# PIC.net
KiCad netlist of a schematic drawn in Altium Designer
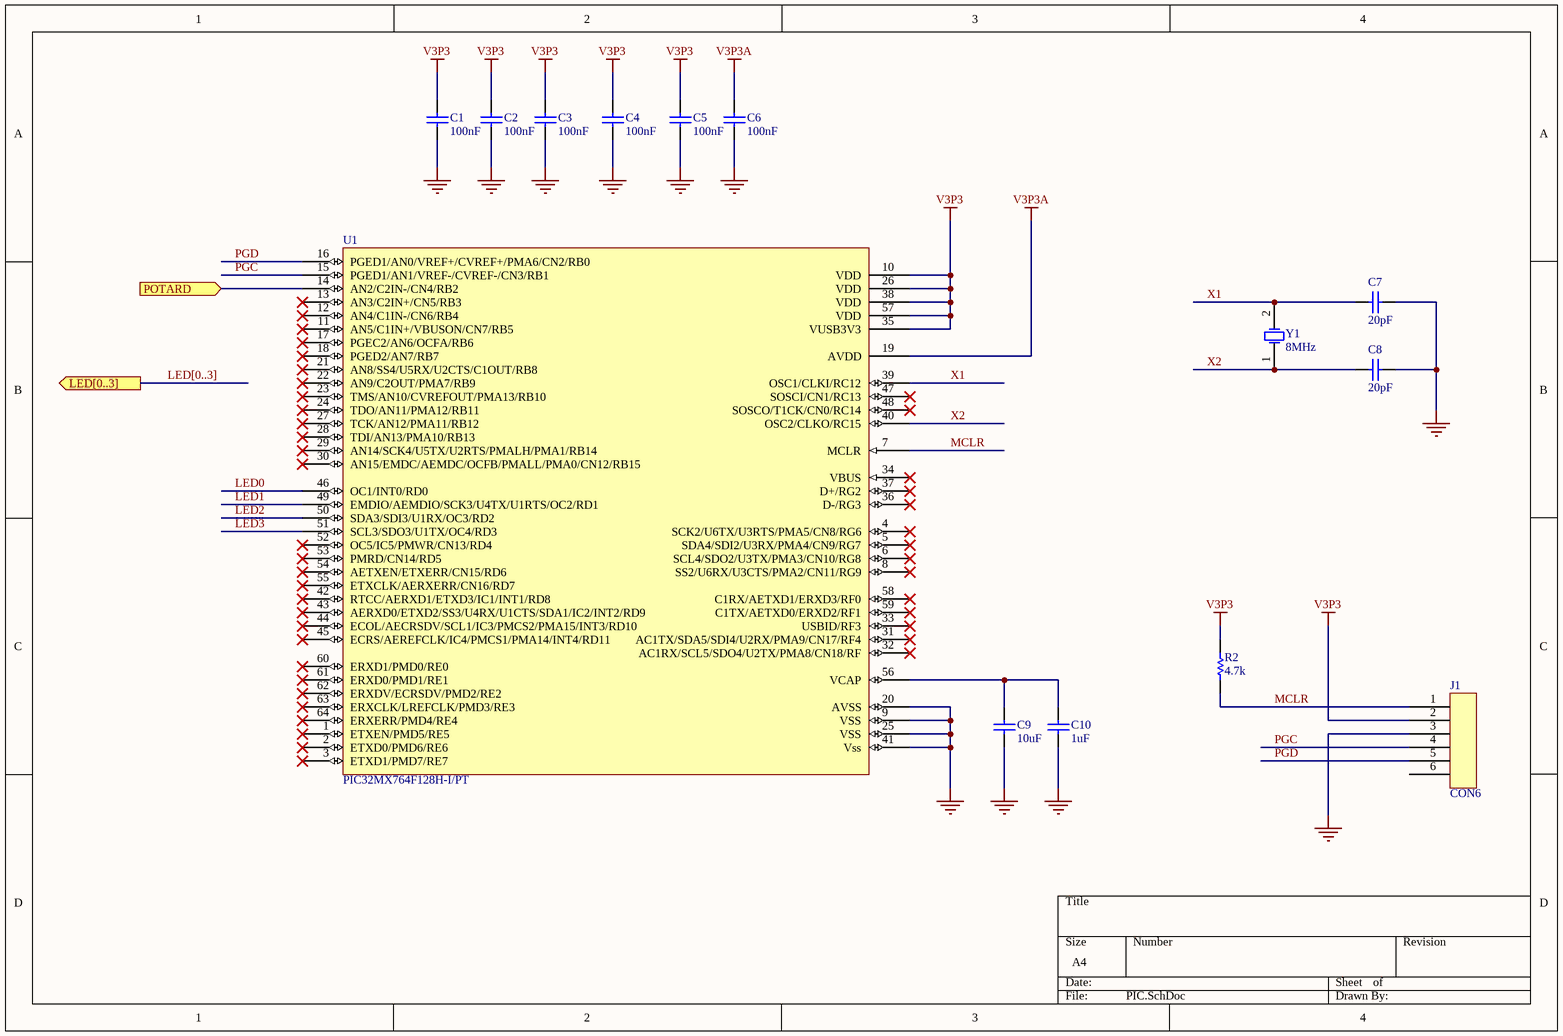
[diagram p0: PIC.SchDoc]

(export (version "E")
  (design (tool "Eeschema 10.0.6"))
  (components
    (comp (ref "C1")
      (value "100nF")
      (footprint "CAPC1608N")
      (description "Capacitor")
      (fields (field (name "PUBLISHER") "Altium Limited"))
      (libsource (lib "Miscellaneous Devices") (part "Cap"))
    )
    (comp (ref "C2")
      (value "100nF")
      (footprint "CAPC1608N")
      (description "Capacitor")
      (fields (field (name "PUBLISHER") "Altium Limited"))
      (libsource (lib "Miscellaneous Devices") (part "Cap"))
    )
    (comp (ref "C3")
      (value "100nF")
      (footprint "CAPC1608N")
      (description "Capacitor")
      (fields (field (name "PUBLISHER") "Altium Limited"))
      (libsource (lib "Miscellaneous Devices") (part "Cap"))
    )
    (comp (ref "C4")
      (value "100nF")
      (footprint "CAPC1608N")
      (description "Capacitor")
      (fields (field (name "PUBLISHER") "Altium Limited"))
      (libsource (lib "Miscellaneous Devices") (part "Cap"))
    )
    (comp (ref "C5")
      (value "100nF")
      (footprint "CAPC1608N")
      (description "Capacitor")
      (fields (field (name "PUBLISHER") "Altium Limited"))
      (libsource (lib "Miscellaneous Devices") (part "Cap"))
    )
    (comp (ref "C6")
      (value "100nF")
      (footprint "CAPC1608N")
      (description "Capacitor")
      (fields (field (name "PUBLISHER") "Altium Limited"))
      (libsource (lib "Miscellaneous Devices") (part "Cap"))
    )
    (comp (ref "C7")
      (value "20pF")
      (footprint "CAPC1608N")
      (description "Capacitor")
      (fields (field (name "PUBLISHER") "Altium Limited"))
      (libsource (lib "Miscellaneous Devices") (part "Cap"))
    )
    (comp (ref "C8")
      (value "20pF")
      (footprint "CAPC1608N")
      (description "Capacitor")
      (fields (field (name "PUBLISHER") "Altium Limited"))
      (libsource (lib "Miscellaneous Devices") (part "Cap"))
    )
    (comp (ref "C9")
      (value "10uF")
      (footprint "CAPC2012N")
      (description "Capacitor")
      (fields (field (name "PUBLISHER") "Altium Limited"))
      (libsource (lib "Miscellaneous Devices") (part "Cap"))
    )
    (comp (ref "C10")
      (value "1uF")
      (footprint "CAPC1608N")
      (description "Capacitor")
      (fields (field (name "PUBLISHER") "Altium Limited"))
      (libsource (lib "Miscellaneous Devices") (part "Cap"))
    )
    (comp (ref "J1") (value "CON6") (footprint "RJ12_90") (libsource (lib "Schlib1") (part "CON6")))
    (comp (ref "R2")
      (value "4.7k")
      (footprint "RESC1608N")
      (description "Resistor")
      (fields (field (name "PUBLISHER") "Altium Limited"))
      (libsource (lib "Miscellaneous Devices") (part "Res1"))
    )
    (comp (ref "U1")
      (value "PIC32MX764F128H-I/PT")
      (footprint "QFP50P1200X1200X120-64")
      (description "PIC32MX764F128H")
      (libsource (lib "Schlib1") (part "PIC32MX764F128H"))
    )
    (comp (ref "Y1")
      (value "8MHz")
      (footprint "XTAL139X50X45")
      (description "Crystal Oscillator")
      (fields (field (name "PUBLISHER") "Altium Limited"))
      (libsource (lib "Miscellaneous Devices") (part "XTAL"))
    )
  )
  (nets
    (net (code "1") (name "/LED0") (class "Default")
      (node (ref "U1") (pin "46") (pinfunction "OC1/INT0/RD0_46") (pintype "bidirectional"))
    )
    (net (code "2") (name "/LED1") (class "Default")
      (node (ref "U1") (pin "49") (pinfunction "EMDIO/AEMDIO/SCK3/U4TX/U1RTS/OC2/RD1_49") (pintype "bidirectional"))
    )
    (net (code "3") (name "/LED2") (class "Default")
      (node (ref "U1") (pin "50") (pinfunction "SDA3/SDI3/U1RX/OC3/RD2_50") (pintype "bidirectional"))
    )
    (net (code "4") (name "/LED3") (class "Default")
      (node (ref "U1") (pin "51") (pinfunction "SCL3/SDO3/U1TX/OC4/RD3_51") (pintype "bidirectional"))
    )
    (net (code "6") (name "/MCLR") (class "Default")
      (node (ref "J1") (pin "1") (pintype "power_in"))
      (node (ref "R2") (pin "1") (pinfunction "1_1") (pintype "passive"))
      (node (ref "U1") (pin "7") (pinfunction "MCLR_7") (pintype "input"))
    )
    (net (code "7") (name "/PGC") (class "Default")
      (node (ref "J1") (pin "4") (pintype "power_in"))
      (node (ref "U1") (pin "15") (pinfunction "PGED1/AN1/VREF-/CVREF-/CN3/RB1_15") (pintype "bidirectional"))
    )
    (net (code "8") (name "/PGD") (class "Default")
      (node (ref "J1") (pin "5") (pintype "power_in"))
      (node (ref "U1") (pin "16") (pinfunction "PGED1/AN0/VREF+/CVREF+/PMA6/CN2/RB0_16") (pintype "bidirectional"))
    )
    (net (code "9") (name "/POTARD") (class "Default")
      (node (ref "U1") (pin "14") (pinfunction "AN2/C2IN-/CN4/RB2_14") (pintype "bidirectional"))
    )
    (net (code "10") (name "/X1") (class "Default")
      (node (ref "C7") (pin "1") (pinfunction "1_1") (pintype "passive"))
      (node (ref "U1") (pin "39") (pinfunction "OSC1/CLKI/RC12_39") (pintype "bidirectional"))
      (node (ref "Y1") (pin "2") (pinfunction "OSC2_2") (pintype "passive"))
    )
    (net (code "11") (name "/X2") (class "Default")
      (node (ref "C8") (pin "1") (pinfunction "1_1") (pintype "passive"))
      (node (ref "U1") (pin "40") (pinfunction "OSC2/CLKO/RC15_40") (pintype "bidirectional"))
      (node (ref "Y1") (pin "1") (pinfunction "OSC1_1") (pintype "passive"))
    )
    (net (code "12") (name "GND") (class "Default")
      (node (ref "C1") (pin "1") (pinfunction "1_1") (pintype "passive"))
      (node (ref "C10") (pin "1") (pinfunction "1_1") (pintype "passive"))
      (node (ref "C2") (pin "1") (pinfunction "1_1") (pintype "passive"))
      (node (ref "C3") (pin "1") (pinfunction "1_1") (pintype "passive"))
      (node (ref "C4") (pin "1") (pinfunction "1_1") (pintype "passive"))
      (node (ref "C5") (pin "1") (pinfunction "1_1") (pintype "passive"))
      (node (ref "C6") (pin "1") (pinfunction "1_1") (pintype "passive"))
      (node (ref "C7") (pin "2") (pinfunction "2_2") (pintype "passive"))
      (node (ref "C8") (pin "2") (pinfunction "2_2") (pintype "passive"))
      (node (ref "C9") (pin "1") (pinfunction "1_1") (pintype "passive"))
      (node (ref "J1") (pin "3") (pintype "power_in"))
      (node (ref "U1") (pin "20") (pinfunction "AVSS_20") (pintype "bidirectional"))
      (node (ref "U1") (pin "25") (pinfunction "VSS_25") (pintype "bidirectional"))
      (node (ref "U1") (pin "41") (pinfunction "Vss_41") (pintype "bidirectional"))
      (node (ref "U1") (pin "9") (pinfunction "VSS_9") (pintype "bidirectional"))
    )
    (net (code "13") (name "Net-(U1-VCAP)") (class "Default")
      (node (ref "C10") (pin "2") (pinfunction "2_2") (pintype "passive"))
      (node (ref "C9") (pin "2") (pinfunction "2_2") (pintype "passive"))
      (node (ref "U1") (pin "56") (pinfunction "VCAP_56") (pintype "bidirectional"))
    )
    (net (code "14") (name "V3P3") (class "Default")
      (node (ref "C1") (pin "2") (pinfunction "2_2") (pintype "passive"))
      (node (ref "C2") (pin "2") (pinfunction "2_2") (pintype "passive"))
      (node (ref "C3") (pin "2") (pinfunction "2_2") (pintype "passive"))
      (node (ref "C4") (pin "2") (pinfunction "2_2") (pintype "passive"))
      (node (ref "C5") (pin "2") (pinfunction "2_2") (pintype "passive"))
      (node (ref "J1") (pin "2") (pintype "power_in"))
      (node (ref "R2") (pin "2") (pinfunction "2_2") (pintype "passive"))
      (node (ref "U1") (pin "10") (pinfunction "VDD_10") (pintype "power_in"))
      (node (ref "U1") (pin "26") (pinfunction "VDD_26") (pintype "power_in"))
      (node (ref "U1") (pin "35") (pinfunction "VUSB3V3_35") (pintype "power_in"))
      (node (ref "U1") (pin "38") (pinfunction "VDD_38") (pintype "power_in"))
      (node (ref "U1") (pin "57") (pinfunction "VDD_57") (pintype "power_in"))
    )
    (net (code "15") (name "V3P3A") (class "Default")
      (node (ref "C6") (pin "2") (pinfunction "2_2") (pintype "passive"))
      (node (ref "U1") (pin "19") (pinfunction "AVDD_19") (pintype "power_in"))
    )
    (net (code "16") (name "unconnected-(J1-Pad6)") (class "Default")
      (node (ref "J1") (pin "6") (pintype "power_in"))
    )
    (net (code "17") (name "unconnected-(U1-AC1RX{slash}SCL5{slash}SDO4{slash}U2TX{slash}PMA8{slash}CN18{slash}RF-Pad32)") (class "Default")
      (node (ref "U1") (pin "32") (pinfunction "AC1RX/SCL5/SDO4/U2TX/PMA8/CN18/RF_32") (pintype "bidirectional+no_connect"))
    )
    (net (code "18") (name "unconnected-(U1-AC1TX{slash}SDA5{slash}SDI4{slash}U2RX{slash}PMA9{slash}CN17{slash}RF4-Pad31)") (class "Default")
      (node (ref "U1") (pin "31") (pinfunction "AC1TX/SDA5/SDI4/U2RX/PMA9/CN17/RF4_31") (pintype "bidirectional+no_connect"))
    )
    (net (code "19") (name "unconnected-(U1-AERXD0{slash}ETXD2{slash}SS3{slash}U4RX{slash}U1CTS{slash}SDA1{slash}IC2{slash}INT2{slash}RD9-Pad43)") (class "Default")
      (node (ref "U1") (pin "43") (pinfunction "AERXD0/ETXD2/SS3/U4RX/U1CTS/SDA1/IC2/INT2/RD9_43") (pintype "bidirectional+no_connect"))
    )
    (net (code "20") (name "unconnected-(U1-AETXEN{slash}ETXERR{slash}CN15{slash}RD6-Pad54)") (class "Default")
      (node (ref "U1") (pin "54") (pinfunction "AETXEN/ETXERR/CN15/RD6_54") (pintype "bidirectional+no_connect"))
    )
    (net (code "21") (name "unconnected-(U1-AN3{slash}C2IN+{slash}CN5{slash}RB3-Pad13)") (class "Default")
      (node (ref "U1") (pin "13") (pinfunction "AN3/C2IN+/CN5/RB3_13") (pintype "bidirectional+no_connect"))
    )
    (net (code "22") (name "unconnected-(U1-AN4{slash}C1IN-{slash}CN6{slash}RB4-Pad12)") (class "Default")
      (node (ref "U1") (pin "12") (pinfunction "AN4/C1IN-/CN6/RB4_12") (pintype "bidirectional+no_connect"))
    )
    (net (code "23") (name "unconnected-(U1-AN5{slash}C1IN+{slash}VBUSON{slash}CN7{slash}RB5-Pad11)") (class "Default")
      (node (ref "U1") (pin "11") (pinfunction "AN5/C1IN+/VBUSON/CN7/RB5_11") (pintype "bidirectional+no_connect"))
    )
    (net (code "24") (name "unconnected-(U1-AN8{slash}SS4{slash}U5RX{slash}U2CTS{slash}C1OUT{slash}RB8-Pad21)") (class "Default")
      (node (ref "U1") (pin "21") (pinfunction "AN8/SS4/U5RX/U2CTS/C1OUT/RB8_21") (pintype "bidirectional+no_connect"))
    )
    (net (code "25") (name "unconnected-(U1-AN9{slash}C2OUT{slash}PMA7{slash}RB9-Pad22)") (class "Default")
      (node (ref "U1") (pin "22") (pinfunction "AN9/C2OUT/PMA7/RB9_22") (pintype "bidirectional+no_connect"))
    )
    (net (code "26") (name "unconnected-(U1-AN14{slash}SCK4{slash}U5TX{slash}U2RTS{slash}PMALH{slash}PMA1{slash}RB14-Pad29)") (class "Default")
      (node (ref "U1") (pin "29") (pinfunction "AN14/SCK4/U5TX/U2RTS/PMALH/PMA1/RB14_29") (pintype "bidirectional+no_connect"))
    )
    (net (code "27") (name "unconnected-(U1-AN15{slash}EMDC{slash}AEMDC{slash}OCFB{slash}PMALL{slash}PMA0{slash}CN12{slash}RB15-Pad30)") (class "Default")
      (node (ref "U1") (pin "30") (pinfunction "AN15/EMDC/AEMDC/OCFB/PMALL/PMA0/CN12/RB15_30") (pintype "bidirectional+no_connect"))
    )
    (net (code "28") (name "unconnected-(U1-C1RX{slash}AETXD1{slash}ERXD3{slash}RF0-Pad58)") (class "Default")
      (node (ref "U1") (pin "58") (pinfunction "C1RX/AETXD1/ERXD3/RF0_58") (pintype "bidirectional+no_connect"))
    )
    (net (code "29") (name "unconnected-(U1-C1TX{slash}AETXD0{slash}ERXD2{slash}RF1-Pad59)") (class "Default")
      (node (ref "U1") (pin "59") (pinfunction "C1TX/AETXD0/ERXD2/RF1_59") (pintype "bidirectional+no_connect"))
    )
    (net (code "30") (name "unconnected-(U1-D+{slash}RG2-Pad37)") (class "Default")
      (node (ref "U1") (pin "37") (pinfunction "D+/RG2_37") (pintype "bidirectional+no_connect"))
    )
    (net (code "31") (name "unconnected-(U1-D-{slash}RG3-Pad36)") (class "Default")
      (node (ref "U1") (pin "36") (pinfunction "D-/RG3_36") (pintype "bidirectional+no_connect"))
    )
    (net (code "32") (name "unconnected-(U1-ECOL{slash}AECRSDV{slash}SCL1{slash}IC3{slash}PMCS2{slash}PMA15{slash}INT3{slash}RD10-Pad44)") (class "Default")
      (node (ref "U1") (pin "44") (pinfunction "ECOL/AECRSDV/SCL1/IC3/PMCS2/PMA15/INT3/RD10_44") (pintype "bidirectional+no_connect"))
    )
    (net (code "33") (name "unconnected-(U1-ECRS{slash}AEREFCLK{slash}IC4{slash}PMCS1{slash}PMA14{slash}INT4{slash}RD11-Pad45)") (class "Default")
      (node (ref "U1") (pin "45") (pinfunction "ECRS/AEREFCLK/IC4/PMCS1/PMA14/INT4/RD11_45") (pintype "bidirectional+no_connect"))
    )
    (net (code "34") (name "unconnected-(U1-ERXCLK{slash}LREFCLK{slash}PMD3{slash}RE3-Pad63)") (class "Default")
      (node (ref "U1") (pin "63") (pinfunction "ERXCLK/LREFCLK/PMD3/RE3_63") (pintype "bidirectional+no_connect"))
    )
    (net (code "35") (name "unconnected-(U1-ERXD0{slash}PMD1{slash}RE1-Pad61)") (class "Default")
      (node (ref "U1") (pin "61") (pinfunction "ERXD0/PMD1/RE1_61") (pintype "bidirectional+no_connect"))
    )
    (net (code "36") (name "unconnected-(U1-ERXD1{slash}PMD0{slash}RE0-Pad60)") (class "Default")
      (node (ref "U1") (pin "60") (pinfunction "ERXD1/PMD0/RE0_60") (pintype "bidirectional+no_connect"))
    )
    (net (code "37") (name "unconnected-(U1-ERXDV{slash}ECRSDV{slash}PMD2{slash}RE2-Pad62)") (class "Default")
      (node (ref "U1") (pin "62") (pinfunction "ERXDV/ECRSDV/PMD2/RE2_62") (pintype "bidirectional+no_connect"))
    )
    (net (code "38") (name "unconnected-(U1-ERXERR{slash}PMD4{slash}RE4-Pad64)") (class "Default")
      (node (ref "U1") (pin "64") (pinfunction "ERXERR/PMD4/RE4_64") (pintype "bidirectional+no_connect"))
    )
    (net (code "39") (name "unconnected-(U1-ETXCLK{slash}AERXERR{slash}CN16{slash}RD7-Pad55)") (class "Default")
      (node (ref "U1") (pin "55") (pinfunction "ETXCLK/AERXERR/CN16/RD7_55") (pintype "bidirectional+no_connect"))
    )
    (net (code "40") (name "unconnected-(U1-ETXD0{slash}PMD6{slash}RE6-Pad2)") (class "Default")
      (node (ref "U1") (pin "2") (pinfunction "ETXD0/PMD6/RE6_2") (pintype "bidirectional+no_connect"))
    )
    (net (code "41") (name "unconnected-(U1-ETXD1{slash}PMD7{slash}RE7-Pad3)") (class "Default")
      (node (ref "U1") (pin "3") (pinfunction "ETXD1/PMD7/RE7_3") (pintype "bidirectional+no_connect"))
    )
    (net (code "42") (name "unconnected-(U1-ETXEN{slash}PMD5{slash}RE5-Pad1)") (class "Default")
      (node (ref "U1") (pin "1") (pinfunction "ETXEN/PMD5/RE5_1") (pintype "bidirectional+no_connect"))
    )
    (net (code "43") (name "unconnected-(U1-OC5{slash}IC5{slash}PMWR{slash}CN13{slash}RD4-Pad52)") (class "Default")
      (node (ref "U1") (pin "52") (pinfunction "OC5/IC5/PMWR/CN13/RD4_52") (pintype "bidirectional+no_connect"))
    )
    (net (code "44") (name "unconnected-(U1-PGEC2{slash}AN6{slash}OCFA{slash}RB6-Pad17)") (class "Default")
      (node (ref "U1") (pin "17") (pinfunction "PGEC2/AN6/OCFA/RB6_17") (pintype "bidirectional+no_connect"))
    )
    (net (code "45") (name "unconnected-(U1-PGED2{slash}AN7{slash}RB7-Pad18)") (class "Default")
      (node (ref "U1") (pin "18") (pinfunction "PGED2/AN7/RB7_18") (pintype "bidirectional+no_connect"))
    )
    (net (code "46") (name "unconnected-(U1-PMRD{slash}CN14{slash}RD5-Pad53)") (class "Default")
      (node (ref "U1") (pin "53") (pinfunction "PMRD/CN14/RD5_53") (pintype "bidirectional+no_connect"))
    )
    (net (code "47") (name "unconnected-(U1-RTCC{slash}AERXD1{slash}ETXD3{slash}IC1{slash}INT1{slash}RD8-Pad42)") (class "Default")
      (node (ref "U1") (pin "42") (pinfunction "RTCC/AERXD1/ETXD3/IC1/INT1/RD8_42") (pintype "bidirectional+no_connect"))
    )
    (net (code "48") (name "unconnected-(U1-SCK2{slash}U6TX{slash}U3RTS{slash}PMA5{slash}CN8{slash}RG6-Pad4)") (class "Default")
      (node (ref "U1") (pin "4") (pinfunction "SCK2/U6TX/U3RTS/PMA5/CN8/RG6_4") (pintype "bidirectional+no_connect"))
    )
    (net (code "49") (name "unconnected-(U1-SCL4{slash}SDO2{slash}U3TX{slash}PMA3{slash}CN10{slash}RG8-Pad6)") (class "Default")
      (node (ref "U1") (pin "6") (pinfunction "SCL4/SDO2/U3TX/PMA3/CN10/RG8_6") (pintype "bidirectional+no_connect"))
    )
    (net (code "50") (name "unconnected-(U1-SDA4{slash}SDI2{slash}U3RX{slash}PMA4{slash}CN9{slash}RG7-Pad5)") (class "Default")
      (node (ref "U1") (pin "5") (pinfunction "SDA4/SDI2/U3RX/PMA4/CN9/RG7_5") (pintype "bidirectional+no_connect"))
    )
    (net (code "51") (name "unconnected-(U1-SOSCI{slash}CN1{slash}RC13-Pad47)") (class "Default")
      (node (ref "U1") (pin "47") (pinfunction "SOSCI/CN1/RC13_47") (pintype "bidirectional+no_connect"))
    )
    (net (code "52") (name "unconnected-(U1-SOSCO{slash}T1CK{slash}CN0{slash}RC14-Pad48)") (class "Default")
      (node (ref "U1") (pin "48") (pinfunction "SOSCO/T1CK/CN0/RC14_48") (pintype "bidirectional+no_connect"))
    )
    (net (code "53") (name "unconnected-(U1-SS2{slash}U6RX{slash}U3CTS{slash}PMA2{slash}CN11{slash}RG9-Pad8)") (class "Default")
      (node (ref "U1") (pin "8") (pinfunction "SS2/U6RX/U3CTS/PMA2/CN11/RG9_8") (pintype "bidirectional+no_connect"))
    )
    (net (code "54") (name "unconnected-(U1-TCK{slash}AN12{slash}PMA11{slash}RB12-Pad27)") (class "Default")
      (node (ref "U1") (pin "27") (pinfunction "TCK/AN12/PMA11/RB12_27") (pintype "bidirectional+no_connect"))
    )
    (net (code "55") (name "unconnected-(U1-TDI{slash}AN13{slash}PMA10{slash}RB13-Pad28)") (class "Default")
      (node (ref "U1") (pin "28") (pinfunction "TDI/AN13/PMA10/RB13_28") (pintype "bidirectional+no_connect"))
    )
    (net (code "56") (name "unconnected-(U1-TDO{slash}AN11{slash}PMA12{slash}RB11-Pad24)") (class "Default")
      (node (ref "U1") (pin "24") (pinfunction "TDO/AN11/PMA12/RB11_24") (pintype "bidirectional+no_connect"))
    )
    (net (code "57") (name "unconnected-(U1-TMS{slash}AN10{slash}CVREFOUT{slash}PMA13{slash}RB10-Pad23)") (class "Default")
      (node (ref "U1") (pin "23") (pinfunction "TMS/AN10/CVREFOUT/PMA13/RB10_23") (pintype "bidirectional+no_connect"))
    )
    (net (code "58") (name "unconnected-(U1-USBID{slash}RF3-Pad33)") (class "Default")
      (node (ref "U1") (pin "33") (pinfunction "USBID/RF3_33") (pintype "bidirectional+no_connect"))
    )
    (net (code "59") (name "unconnected-(U1-VBUS-Pad34)") (class "Default")
      (node (ref "U1") (pin "34") (pinfunction "VBUS_34") (pintype "input+no_connect"))
    )
  )
)
